# alimentadorV2.net
KiCad netlist of a schematic drawn in EAGLE
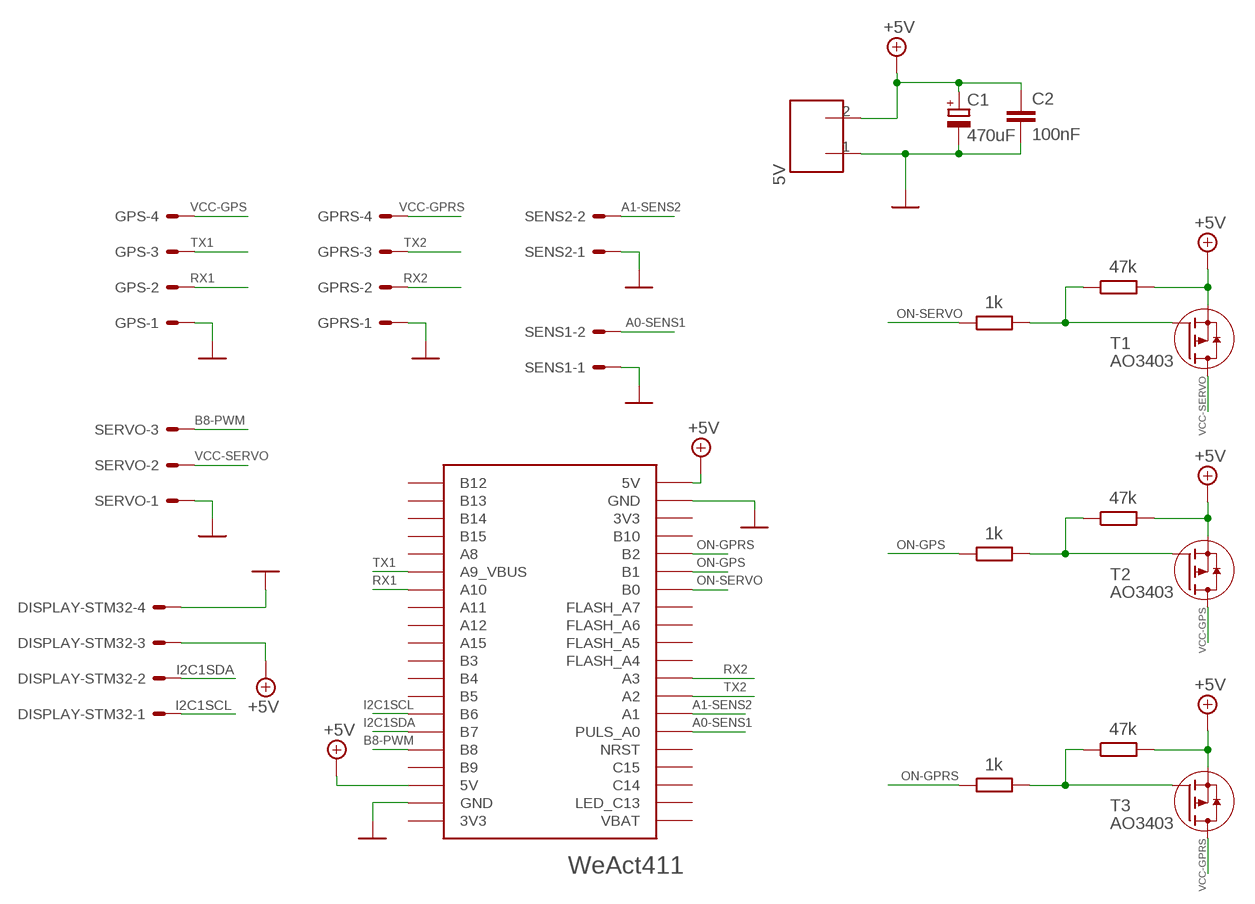
[diagram p0: schematic, sheet 1]

(export (version "E")
  (design (tool "Eeschema 10.0.6"))
  (components
    (comp (ref "5V")
      (value "CONECTOR_2P-3.81")
      (footprint "eagle-import:CON2P-3.81")
      (libsource (lib "eagle-import") (part "CONECTOR_2P-3.81"))
    )
    (comp (ref "C1")
      (value "470uF")
      (footprint "eagle-import:E5-10,5")
      (libsource (lib "eagle-import") (part "CPOL-EUE5-10.5"))
    )
    (comp (ref "C2")
      (value "100nF")
      (footprint "eagle-import:C1206")
      (libsource (lib "eagle-import") (part "C-EUC1206"))
    )
    (comp (ref "DISPLAY-STM32")
      (value "22-05-7048-04")
      (footprint "eagle-import:7395-04")
      (libsource (lib "eagle-import") (part "22-?-0405-7048"))
    )
    (comp (ref "GPRS")
      (value "22-27-2041-04")
      (footprint "eagle-import:6410-04")
      (libsource (lib "eagle-import") (part "22-?-0427-2041"))
    )
    (comp (ref "GPS")
      (value "22-27-2041-04")
      (footprint "eagle-import:6410-04")
      (libsource (lib "eagle-import") (part "22-?-0427-2041"))
    )
    (comp (ref "R1")
      (value "47k")
      (footprint "eagle-import:R1206")
      (libsource (lib "eagle-import") (part "R-EU_R1206"))
    )
    (comp (ref "R2")
      (value "47k")
      (footprint "eagle-import:R1206")
      (libsource (lib "eagle-import") (part "R-EU_R1206"))
    )
    (comp (ref "R3")
      (value "1k")
      (footprint "eagle-import:R1206")
      (libsource (lib "eagle-import") (part "R-EU_R1206"))
    )
    (comp (ref "R4")
      (value "1k")
      (footprint "eagle-import:R1206")
      (libsource (lib "eagle-import") (part "R-EU_R1206"))
    )
    (comp (ref "R5")
      (value "47k")
      (footprint "eagle-import:R1206")
      (libsource (lib "eagle-import") (part "R-EU_R1206"))
    )
    (comp (ref "R6")
      (value "1k")
      (footprint "eagle-import:R1206")
      (libsource (lib "eagle-import") (part "R-EU_R1206"))
    )
    (comp (ref "SENS1")
      (value "22-27-2021-02")
      (footprint "eagle-import:6410-02")
      (libsource (lib "eagle-import") (part "22-?-0227-2021"))
    )
    (comp (ref "SENS2")
      (value "22-27-2021-02")
      (footprint "eagle-import:6410-02")
      (libsource (lib "eagle-import") (part "22-?-0227-2021"))
    )
    (comp (ref "SERVO")
      (value "22-27-2031-03")
      (footprint "eagle-import:6410-03")
      (libsource (lib "eagle-import") (part "22-?-0327-2031"))
    )
    (comp (ref "T1")
      (value "AO3403")
      (footprint "eagle-import:SOT23")
      (libsource (lib "eagle-import") (part "AO3403"))
    )
    (comp (ref "T2")
      (value "AO3403")
      (footprint "eagle-import:SOT23")
      (libsource (lib "eagle-import") (part "AO3403"))
    )
    (comp (ref "T3")
      (value "AO3403")
      (footprint "eagle-import:SOT23")
      (libsource (lib "eagle-import") (part "AO3403"))
    )
    (comp (ref "U$2")
      (value "WEACT411")
      (footprint "eagle-import:WEACT411")
      (libsource (lib "eagle-import") (part "WEACT411"))
    )
  )
  (nets
    (net (code "1") (name "+5V") (class "Default")
      (node (ref "5V") (pin "2") (pinfunction "2_2") (pintype "bidirectional"))
      (node (ref "C1") (pin "+") (pinfunction "+_+") (pintype "passive"))
      (node (ref "C2") (pin "1") (pinfunction "1_1") (pintype "passive"))
      (node (ref "DISPLAY-STM32") (pin "3") (pinfunction "S_3") (pintype "passive"))
      (node (ref "R1") (pin "2") (pinfunction "2_2") (pintype "passive"))
      (node (ref "R2") (pin "2") (pinfunction "2_2") (pintype "passive"))
      (node (ref "R5") (pin "2") (pinfunction "2_2") (pintype "passive"))
      (node (ref "T1") (pin "2") (pinfunction "S_2") (pintype "passive"))
      (node (ref "T2") (pin "2") (pinfunction "S_2") (pintype "passive"))
      (node (ref "T3") (pin "2") (pinfunction "S_2") (pintype "passive"))
      (node (ref "U$2") (pin "5V@1") (pinfunction "5V_5V@1") (pintype "power_in"))
      (node (ref "U$2") (pin "5V@2") (pinfunction "5V_5V@2") (pintype "power_in"))
    )
    (net (code "2") (name "/A0-SENS1") (class "Default")
      (node (ref "SENS1") (pin "2") (pinfunction "S_2") (pintype "passive"))
      (node (ref "U$2") (pin "A0") (pinfunction "PULS_A0_A0") (pintype "bidirectional"))
    )
    (net (code "3") (name "/A1-SENS2") (class "Default")
      (node (ref "SENS2") (pin "2") (pinfunction "S_2") (pintype "passive"))
      (node (ref "U$2") (pin "A1") (pinfunction "A1_A1") (pintype "bidirectional"))
    )
    (net (code "4") (name "/B8-PWM") (class "Default")
      (node (ref "SERVO") (pin "3") (pinfunction "S_3") (pintype "passive"))
      (node (ref "U$2") (pin "B8") (pinfunction "B8_B8") (pintype "bidirectional"))
    )
    (net (code "5") (name "/I2C1SCL") (class "Default")
      (node (ref "DISPLAY-STM32") (pin "1") (pinfunction "S_1") (pintype "passive"))
      (node (ref "U$2") (pin "B6") (pinfunction "B6_B6") (pintype "bidirectional"))
    )
    (net (code "6") (name "/I2C1SDA") (class "Default")
      (node (ref "DISPLAY-STM32") (pin "2") (pinfunction "S_2") (pintype "passive"))
      (node (ref "U$2") (pin "B7") (pinfunction "B7_B7") (pintype "bidirectional"))
    )
    (net (code "7") (name "/ON-GPRS") (class "Default")
      (node (ref "R6") (pin "1") (pinfunction "1_1") (pintype "passive"))
      (node (ref "U$2") (pin "B2") (pinfunction "B2_B2") (pintype "bidirectional"))
    )
    (net (code "8") (name "/ON-GPS") (class "Default")
      (node (ref "R4") (pin "1") (pinfunction "1_1") (pintype "passive"))
      (node (ref "U$2") (pin "B1") (pinfunction "B1_B1") (pintype "bidirectional"))
    )
    (net (code "9") (name "/ON-SERVO") (class "Default")
      (node (ref "R3") (pin "1") (pinfunction "1_1") (pintype "passive"))
      (node (ref "U$2") (pin "B0") (pinfunction "B0_B0") (pintype "bidirectional"))
    )
    (net (code "10") (name "/RX1") (class "Default")
      (node (ref "GPS") (pin "2") (pinfunction "S_2") (pintype "passive"))
      (node (ref "U$2") (pin "A10") (pinfunction "A10_A10") (pintype "bidirectional"))
    )
    (net (code "11") (name "/RX2") (class "Default")
      (node (ref "GPRS") (pin "2") (pinfunction "S_2") (pintype "passive"))
      (node (ref "U$2") (pin "A3") (pinfunction "A3_A3") (pintype "bidirectional"))
    )
    (net (code "12") (name "/TX1") (class "Default")
      (node (ref "GPS") (pin "3") (pinfunction "S_3") (pintype "passive"))
      (node (ref "U$2") (pin "A9") (pinfunction "A9_VBUS_A9") (pintype "bidirectional"))
    )
    (net (code "13") (name "/TX2") (class "Default")
      (node (ref "GPRS") (pin "3") (pinfunction "S_3") (pintype "passive"))
      (node (ref "U$2") (pin "A2") (pinfunction "A2_A2") (pintype "bidirectional"))
    )
    (net (code "14") (name "/VBAT") (class "Default")
      (node (ref "U$2") (pin "VBAT") (pinfunction "VBAT_VBAT") (pintype "power_in"))
    )
    (net (code "15") (name "/VCC-GPRS") (class "Default")
      (node (ref "GPRS") (pin "4") (pinfunction "S_4") (pintype "passive"))
      (node (ref "T3") (pin "3") (pinfunction "D_3") (pintype "passive"))
    )
    (net (code "16") (name "/VCC-GPS") (class "Default")
      (node (ref "GPS") (pin "4") (pinfunction "S_4") (pintype "passive"))
      (node (ref "T2") (pin "3") (pinfunction "D_3") (pintype "passive"))
    )
    (net (code "17") (name "/VCC-SERVO") (class "Default")
      (node (ref "SERVO") (pin "2") (pinfunction "S_2") (pintype "passive"))
      (node (ref "T1") (pin "3") (pinfunction "D_3") (pintype "passive"))
    )
    (net (code "18") (name "GND") (class "Default")
      (node (ref "5V") (pin "1") (pinfunction "1_1") (pintype "bidirectional"))
      (node (ref "C1") (pin "-") (pinfunction "-_-") (pintype "passive"))
      (node (ref "C2") (pin "2") (pinfunction "2_2") (pintype "passive"))
      (node (ref "DISPLAY-STM32") (pin "4") (pinfunction "S_4") (pintype "passive"))
      (node (ref "GPRS") (pin "1") (pinfunction "S_1") (pintype "passive"))
      (node (ref "GPS") (pin "1") (pinfunction "S_1") (pintype "passive"))
      (node (ref "SENS1") (pin "1") (pinfunction "S_1") (pintype "passive"))
      (node (ref "SENS2") (pin "1") (pinfunction "S_1") (pintype "passive"))
      (node (ref "SERVO") (pin "1") (pinfunction "S_1") (pintype "passive"))
      (node (ref "U$2") (pin "GND@1") (pinfunction "GND_GND@1") (pintype "power_in"))
      (node (ref "U$2") (pin "GND@2") (pinfunction "GND_GND@2") (pintype "power_in"))
    )
    (net (code "19") (name "Net-(T1-G)") (class "Default")
      (node (ref "R2") (pin "1") (pinfunction "1_1") (pintype "passive"))
      (node (ref "R3") (pin "2") (pinfunction "2_2") (pintype "passive"))
      (node (ref "T1") (pin "1") (pinfunction "G_1") (pintype "passive"))
    )
    (net (code "20") (name "Net-(T2-G)") (class "Default")
      (node (ref "R1") (pin "1") (pinfunction "1_1") (pintype "passive"))
      (node (ref "R4") (pin "2") (pinfunction "2_2") (pintype "passive"))
      (node (ref "T2") (pin "1") (pinfunction "G_1") (pintype "passive"))
    )
    (net (code "21") (name "Net-(T3-G)") (class "Default")
      (node (ref "R5") (pin "1") (pinfunction "1_1") (pintype "passive"))
      (node (ref "R6") (pin "2") (pinfunction "2_2") (pintype "passive"))
      (node (ref "T3") (pin "1") (pinfunction "G_1") (pintype "passive"))
    )
    (net (code "22") (name "unconnected-(U$2-3V3-Pad3V3@1)") (class "Default")
      (node (ref "U$2") (pin "3V3@1") (pinfunction "3V3_3V3@1") (pintype "bidirectional"))
    )
    (net (code "23") (name "unconnected-(U$2-3V3-Pad3V3@2)") (class "Default")
      (node (ref "U$2") (pin "3V3@2") (pinfunction "3V3_3V3@2") (pintype "bidirectional"))
    )
    (net (code "24") (name "unconnected-(U$2-FLASH_A4-PadA4)") (class "Default")
      (node (ref "U$2") (pin "A4") (pinfunction "FLASH_A4_A4") (pintype "bidirectional"))
    )
    (net (code "25") (name "unconnected-(U$2-FLASH_A5-PadA5)") (class "Default")
      (node (ref "U$2") (pin "A5") (pinfunction "FLASH_A5_A5") (pintype "bidirectional"))
    )
    (net (code "26") (name "unconnected-(U$2-FLASH_A6-PadA6)") (class "Default")
      (node (ref "U$2") (pin "A6") (pinfunction "FLASH_A6_A6") (pintype "bidirectional"))
    )
    (net (code "27") (name "unconnected-(U$2-FLASH_A7-PadA7)") (class "Default")
      (node (ref "U$2") (pin "A7") (pinfunction "FLASH_A7_A7") (pintype "bidirectional"))
    )
    (net (code "28") (name "unconnected-(U$2-LED_C13-PadC13)") (class "Default")
      (node (ref "U$2") (pin "C13") (pinfunction "LED_C13_C13") (pintype "bidirectional"))
    )
    (net (code "29") (name "unconnected-(U$2-PadA8)") (class "Default")
      (node (ref "U$2") (pin "A8") (pinfunction "A8_A8") (pintype "bidirectional"))
    )
    (net (code "30") (name "unconnected-(U$2-PadA11)") (class "Default")
      (node (ref "U$2") (pin "A11") (pinfunction "A11_A11") (pintype "bidirectional"))
    )
    (net (code "31") (name "unconnected-(U$2-PadA12)") (class "Default")
      (node (ref "U$2") (pin "A12") (pinfunction "A12_A12") (pintype "bidirectional"))
    )
    (net (code "32") (name "unconnected-(U$2-PadA15)") (class "Default")
      (node (ref "U$2") (pin "A15") (pinfunction "A15_A15") (pintype "bidirectional"))
    )
    (net (code "33") (name "unconnected-(U$2-PadB3)") (class "Default")
      (node (ref "U$2") (pin "B3") (pinfunction "B3_B3") (pintype "bidirectional"))
    )
    (net (code "34") (name "unconnected-(U$2-PadB4)") (class "Default")
      (node (ref "U$2") (pin "B4") (pinfunction "B4_B4") (pintype "bidirectional"))
    )
    (net (code "35") (name "unconnected-(U$2-PadB5)") (class "Default")
      (node (ref "U$2") (pin "B5") (pinfunction "B5_B5") (pintype "bidirectional"))
    )
    (net (code "36") (name "unconnected-(U$2-PadB9)") (class "Default")
      (node (ref "U$2") (pin "B9") (pinfunction "B9_B9") (pintype "bidirectional"))
    )
    (net (code "37") (name "unconnected-(U$2-PadB10)") (class "Default")
      (node (ref "U$2") (pin "B10") (pinfunction "B10_B10") (pintype "bidirectional"))
    )
    (net (code "38") (name "unconnected-(U$2-PadB12)") (class "Default")
      (node (ref "U$2") (pin "B12") (pinfunction "B12_B12") (pintype "bidirectional"))
    )
    (net (code "39") (name "unconnected-(U$2-PadB13)") (class "Default")
      (node (ref "U$2") (pin "B13") (pinfunction "B13_B13") (pintype "bidirectional"))
    )
    (net (code "40") (name "unconnected-(U$2-PadB14)") (class "Default")
      (node (ref "U$2") (pin "B14") (pinfunction "B14_B14") (pintype "bidirectional"))
    )
    (net (code "41") (name "unconnected-(U$2-PadB15)") (class "Default")
      (node (ref "U$2") (pin "B15") (pinfunction "B15_B15") (pintype "bidirectional"))
    )
    (net (code "42") (name "unconnected-(U$2-PadC14)") (class "Default")
      (node (ref "U$2") (pin "C14") (pinfunction "C14_C14") (pintype "bidirectional"))
    )
    (net (code "43") (name "unconnected-(U$2-PadC15)") (class "Default")
      (node (ref "U$2") (pin "C15") (pinfunction "C15_C15") (pintype "bidirectional"))
    )
    (net (code "44") (name "unconnected-(U$2-PadNRST)") (class "Default")
      (node (ref "U$2") (pin "NRST") (pinfunction "NRST_NRST") (pintype "bidirectional"))
    )
  )
)
